# high_fre_amp.net
KiCad netlist of a schematic drawn in Altium Designer
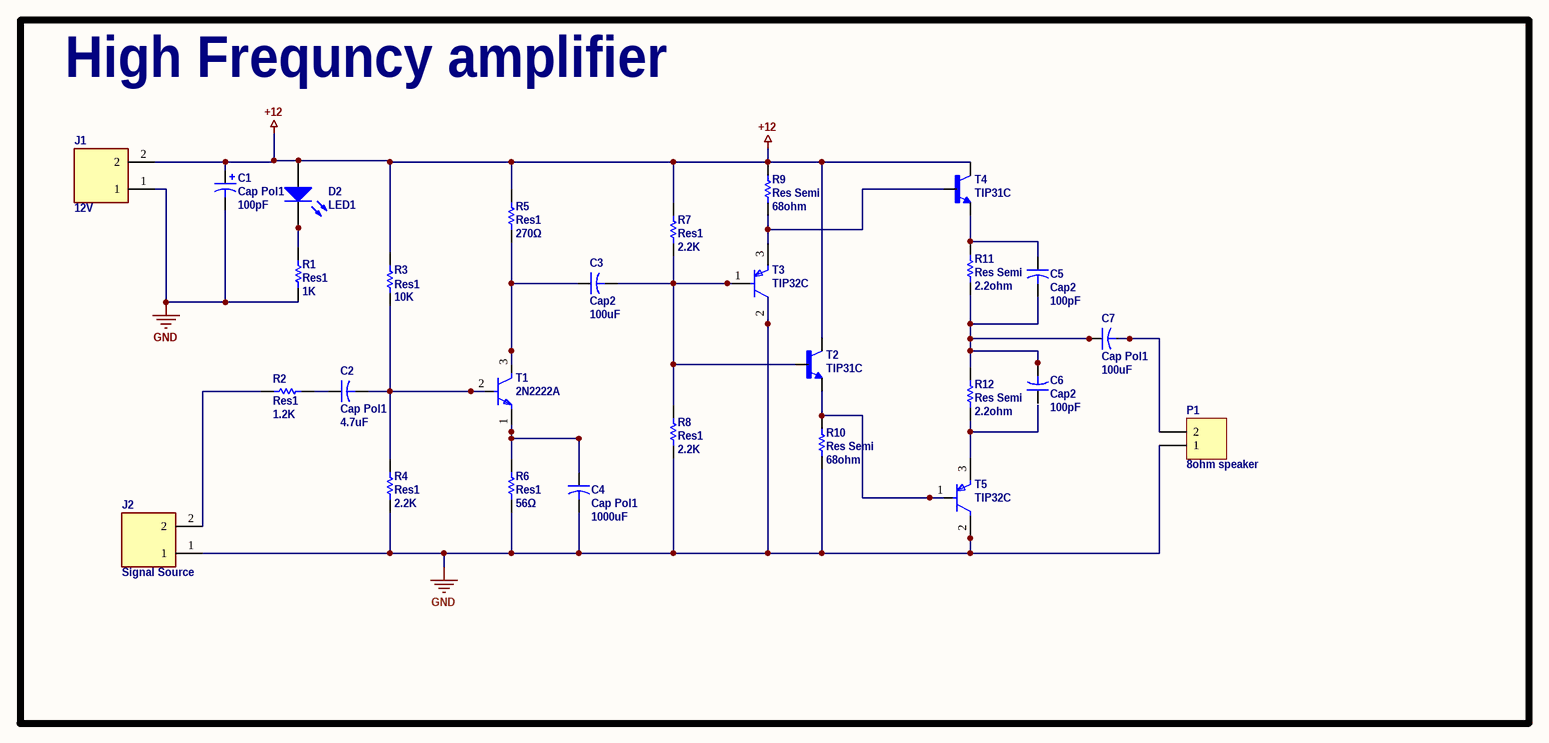
[diagram p0: high_fre_amp.SchDoc]

(export (version "E")
  (design (tool "Eeschema 10.0.6"))
  (components
    (comp (ref "C1")
      (value "Cap Pol1")
      (footprint "RB7.6-15")
      (description "Polarized Capacitor (Radial)")
      (fields (field (name "ALTIUM_VALUE") "100pF") (field (name "PUBLISHER") "Altium Limited"))
      (libsource (lib "Miscellaneous Devices") (part "Cap Pol1"))
    )
    (comp (ref "C2")
      (value "Cap Pol1")
      (footprint "RB7.6-15")
      (description "Capacitor")
      (fields (field (name "ALTIUM_VALUE") "4.7uF") (field (name "PUBLISHER") "Altium Limited"))
      (libsource (lib "Miscellaneous Devices") (part "Cap2"))
    )
    (comp (ref "C3")
      (value "Cap2")
      (footprint "CAPR5-4X5")
      (description "Capacitor")
      (fields (field (name "ALTIUM_VALUE") "100uF") (field (name "PUBLISHER") "Altium Limited"))
      (libsource (lib "Miscellaneous Devices") (part "Cap2"))
    )
    (comp (ref "C4")
      (value "Cap Pol1")
      (footprint "RB7.6-15")
      (description "Capacitor")
      (fields (field (name "ALTIUM_VALUE") "1000uF") (field (name "PUBLISHER") "Altium Limited"))
      (libsource (lib "Miscellaneous Devices") (part "Cap2"))
    )
    (comp (ref "C5")
      (value "Cap2")
      (footprint "CAPR5-4X5")
      (description "Capacitor")
      (fields (field (name "ALTIUM_VALUE") "100pF") (field (name "PUBLISHER") "Altium Limited"))
      (libsource (lib "Miscellaneous Devices") (part "Cap2"))
    )
    (comp (ref "C6")
      (value "Cap2")
      (footprint "CAPR5-4X5")
      (description "Capacitor")
      (fields (field (name "ALTIUM_VALUE") "100pF") (field (name "PUBLISHER") "Altium Limited"))
      (libsource (lib "Miscellaneous Devices") (part "Cap2"))
    )
    (comp (ref "C7")
      (value "Cap Pol1")
      (footprint "RB7.6-15")
      (description "Capacitor")
      (fields (field (name "ALTIUM_VALUE") "100uF") (field (name "PUBLISHER") "Altium Limited"))
      (libsource (lib "Miscellaneous Devices") (part "Cap2"))
    )
    (comp (ref "D2")
      (value "LED1")
      (footprint "LED-1")
      (description "Typical RED GaAs LED")
      (fields (field (name "PUBLISHER") "Altium Limited"))
      (libsource (lib "Miscellaneous Devices") (part "LED1"))
    )
    (comp (ref "J1")
      (value "12V")
      (footprint "HANDSON_KF301-2P")
      (description "2 Pin Terminal Block 5mm Pitch")
      (fields (field (name "MP") "KF301-2P"))
      (libsource (lib "KF301-2P") (part "KF301-2P"))
    )
    (comp (ref "J2")
      (value "Signal Source")
      (footprint "HANDSON_KF301-2P")
      (description "2 Pin Terminal Block 5mm Pitch")
      (fields (field (name "MP") "KF301-2P"))
      (libsource (lib "KF301-2P") (part "KF301-2P"))
    )
    (comp (ref "P1")
      (value "8ohm speaker")
      (footprint "HDR1X2")
      (description "Header, 2-Pin")
      (fields (field (name "PUBLISHER") "Altium Limited"))
      (libsource (lib "Miscellaneous Connectors") (part "Header 2"))
    )
    (comp (ref "R1")
      (value "Res1")
      (footprint "AXIAL-0.3")
      (description "Resistor")
      (fields (field (name "ALTIUM_VALUE") "1K") (field (name "PUBLISHER") "Altium Limited"))
      (libsource (lib "Miscellaneous Devices") (part "Res1"))
    )
    (comp (ref "R2")
      (value "Res1")
      (footprint "AXIAL-0.3")
      (description "Resistor")
      (fields (field (name "ALTIUM_VALUE") "1.2K") (field (name "PUBLISHER") "Altium Limited"))
      (libsource (lib "Miscellaneous Devices") (part "Res1"))
    )
    (comp (ref "R3")
      (value "Res1")
      (footprint "AXIAL-0.3")
      (description "Resistor")
      (fields (field (name "ALTIUM_VALUE") "10K") (field (name "PUBLISHER") "Altium Limited"))
      (libsource (lib "Miscellaneous Devices") (part "Res1"))
    )
    (comp (ref "R4")
      (value "Res1")
      (footprint "AXIAL-0.3")
      (description "Resistor")
      (fields (field (name "ALTIUM_VALUE") "2.2K") (field (name "PUBLISHER") "Altium Limited"))
      (libsource (lib "Miscellaneous Devices") (part "Res1"))
    )
    (comp (ref "R5")
      (value "Res1")
      (footprint "AXIAL-0.3")
      (description "Resistor")
      (fields (field (name "ALTIUM_VALUE") "270Ω") (field (name "PUBLISHER") "Altium Limited"))
      (libsource (lib "Miscellaneous Devices") (part "Res1"))
    )
    (comp (ref "R6")
      (value "Res1")
      (footprint "AXIAL-0.3")
      (description "Resistor")
      (fields (field (name "ALTIUM_VALUE") "56Ω") (field (name "PUBLISHER") "Altium Limited"))
      (libsource (lib "Miscellaneous Devices") (part "Res1"))
    )
    (comp (ref "R7")
      (value "Res1")
      (footprint "AXIAL-0.3")
      (description "Resistor")
      (fields (field (name "ALTIUM_VALUE") "2.2K") (field (name "PUBLISHER") "Altium Limited"))
      (libsource (lib "Miscellaneous Devices") (part "Res1"))
    )
    (comp (ref "R8")
      (value "Res1")
      (footprint "AXIAL-0.3")
      (description "Resistor")
      (fields (field (name "ALTIUM_VALUE") "2.2K") (field (name "PUBLISHER") "Altium Limited"))
      (libsource (lib "Miscellaneous Devices") (part "Res1"))
    )
    (comp (ref "R9")
      (value "Res Semi")
      (footprint "AXIAL-0.5")
      (description "Semiconductor Resistor")
      (fields (field (name "ALTIUM_VALUE") "68ohm") (field (name "PUBLISHER") "Altium Limited"))
      (libsource (lib "Miscellaneous Devices") (part "Res Semi"))
    )
    (comp (ref "R10")
      (value "Res Semi")
      (footprint "AXIAL-0.5")
      (description "Semiconductor Resistor")
      (fields (field (name "ALTIUM_VALUE") "68ohm") (field (name "PUBLISHER") "Altium Limited"))
      (libsource (lib "Miscellaneous Devices") (part "Res Semi"))
    )
    (comp (ref "R11")
      (value "Res Semi")
      (footprint "AXIAL-0.5")
      (description "Semiconductor Resistor")
      (fields (field (name "ALTIUM_VALUE") "2.2ohm") (field (name "PUBLISHER") "Altium Limited"))
      (libsource (lib "Miscellaneous Devices") (part "Res Semi"))
    )
    (comp (ref "R12")
      (value "Res Semi")
      (footprint "AXIAL-0.5")
      (description "Semiconductor Resistor")
      (fields (field (name "ALTIUM_VALUE") "2.2ohm") (field (name "PUBLISHER") "Altium Limited"))
      (libsource (lib "Miscellaneous Devices") (part "Res Semi"))
    )
    (comp (ref "T1")
      (value "2N2222A")
      (footprint "FP-2N2222A-MFG")
      (description "T-NPN SI- AUDIO VHF AMP")
      (libsource (lib "Altium Content Vault") (part "a64cbfbad643015290886283bc510aa"))
    )
    (comp (ref "T2")
      (value "TIP31C")
      (footprint "TO220")
      (description "Transistor bipolar (BJT) NPN 100 V 3 A 3 MHz 2 W Orificio pasante TO-220-3")
      (fields (field (name "MF") "ON Semiconductor") (field (name "DIGI-KEY_PART_NUMBER") "TIP31COS-ND"))
      (libsource (lib "TIP31C") (part "TIP31C"))
    )
    (comp (ref "T3")
      (value "TIP32C")
      (footprint "FP-TO-220-P0A0015988-MFG")
      (description "TRANS PNP 100V 3A TO-220")
      (fields
        (field (name "MANUFACTURER") "STMicroelectronics")
        (field (name "OCTOPART") "https://octopart.com/tip32c-stmicroelectronics-353617")
      )
      (libsource (lib "Altium Content Vault") (part "802a31d42ca070764d097f06bc9597f"))
    )
    (comp (ref "T4")
      (value "TIP31C")
      (footprint "TO220")
      (description "Transistor bipolar (BJT) NPN 100 V 3 A 3 MHz 2 W Orificio pasante TO-220-3")
      (fields (field (name "MF") "ON Semiconductor") (field (name "DIGI-KEY_PART_NUMBER") "TIP31COS-ND"))
      (libsource (lib "TIP31C") (part "TIP31C"))
    )
    (comp (ref "T5")
      (value "TIP32C")
      (footprint "FP-TO-220-P0A0015988-MFG")
      (description "TRANS PNP 100V 3A TO-220")
      (fields
        (field (name "MANUFACTURER") "STMicroelectronics")
        (field (name "OCTOPART") "https://octopart.com/tip32c-stmicroelectronics-353617")
      )
      (libsource (lib "Altium Content Vault") (part "802a31d42ca070764d097f06bc9597f"))
    )
  )
  (nets
    (net (code "1") (name "+12") (class "Default")
      (node (ref "C1") (pin "1") (pinfunction "1_1") (pintype "passive"))
      (node (ref "D2") (pin "1") (pinfunction "A_1") (pintype "passive"))
      (node (ref "J1") (pin "2") (pinfunction "2_2") (pintype "passive"))
      (node (ref "R3") (pin "2") (pinfunction "2_2") (pintype "passive"))
      (node (ref "R5") (pin "2") (pinfunction "2_2") (pintype "passive"))
      (node (ref "R7") (pin "2") (pinfunction "2_2") (pintype "passive"))
      (node (ref "R9") (pin "2") (pinfunction "2_2") (pintype "passive"))
      (node (ref "T2") (pin "2") (pinfunction "C_2") (pintype "passive"))
      (node (ref "T4") (pin "2") (pinfunction "C_2") (pintype "passive"))
    )
    (net (code "2") (name "GND") (class "Default")
      (node (ref "C1") (pin "2") (pinfunction "2_2") (pintype "passive"))
      (node (ref "C4") (pin "2") (pinfunction "2_2") (pintype "passive"))
      (node (ref "J1") (pin "1") (pinfunction "1_1") (pintype "passive"))
      (node (ref "J2") (pin "1") (pinfunction "1_1") (pintype "passive"))
      (node (ref "P1") (pin "1") (pinfunction "1_1") (pintype "passive"))
      (node (ref "R1") (pin "2") (pinfunction "2_2") (pintype "passive"))
      (node (ref "R10") (pin "1") (pinfunction "1_1") (pintype "passive"))
      (node (ref "R4") (pin "1") (pinfunction "1_1") (pintype "passive"))
      (node (ref "R6") (pin "1") (pinfunction "1_1") (pintype "passive"))
      (node (ref "R8") (pin "1") (pinfunction "1_1") (pintype "passive"))
      (node (ref "T3") (pin "2") (pinfunction "C_2") (pintype "passive"))
      (node (ref "T5") (pin "2") (pinfunction "C_2") (pintype "passive"))
    )
    (net (code "3") (name "Net-(C2-Pad1)") (class "Default")
      (node (ref "C2") (pin "1") (pinfunction "1_1") (pintype "passive"))
      (node (ref "R2") (pin "2") (pinfunction "2_2") (pintype "passive"))
    )
    (net (code "4") (name "Net-(C5-Pad2)") (class "Default")
      (node (ref "C5") (pin "2") (pinfunction "2_2") (pintype "passive"))
      (node (ref "C6") (pin "2") (pinfunction "2_2") (pintype "passive"))
      (node (ref "C7") (pin "1") (pinfunction "1_1") (pintype "passive"))
      (node (ref "R11") (pin "1") (pinfunction "1_1") (pintype "passive"))
      (node (ref "R12") (pin "2") (pinfunction "2_2") (pintype "passive"))
    )
    (net (code "5") (name "Net-(C7-Pad2)") (class "Default")
      (node (ref "C7") (pin "2") (pinfunction "2_2") (pintype "passive"))
      (node (ref "P1") (pin "2") (pinfunction "2_2") (pintype "passive"))
    )
    (net (code "6") (name "Net-(D2-K)") (class "Default")
      (node (ref "D2") (pin "2") (pinfunction "K_2") (pintype "passive"))
      (node (ref "R1") (pin "1") (pinfunction "1_1") (pintype "passive"))
    )
    (net (code "7") (name "Net-(J2-Pad2)") (class "Default")
      (node (ref "J2") (pin "2") (pinfunction "2_2") (pintype "passive"))
      (node (ref "R2") (pin "1") (pinfunction "1_1") (pintype "passive"))
    )
    (net (code "8") (name "Net-(T1-B)") (class "Default")
      (node (ref "C2") (pin "2") (pinfunction "2_2") (pintype "passive"))
      (node (ref "R3") (pin "1") (pinfunction "1_1") (pintype "passive"))
      (node (ref "R4") (pin "2") (pinfunction "2_2") (pintype "passive"))
      (node (ref "T1") (pin "2") (pinfunction "B_2") (pintype "passive"))
    )
    (net (code "9") (name "Net-(T1-C)") (class "Default")
      (node (ref "C3") (pin "1") (pinfunction "1_1") (pintype "passive"))
      (node (ref "R5") (pin "1") (pinfunction "1_1") (pintype "passive"))
      (node (ref "T1") (pin "3") (pinfunction "C_3") (pintype "passive"))
    )
    (net (code "10") (name "Net-(T1-E)") (class "Default")
      (node (ref "C4") (pin "1") (pinfunction "1_1") (pintype "passive"))
      (node (ref "R6") (pin "2") (pinfunction "2_2") (pintype "passive"))
      (node (ref "T1") (pin "1") (pinfunction "E_1") (pintype "passive"))
    )
    (net (code "11") (name "Net-(T2-B)") (class "Default")
      (node (ref "C3") (pin "2") (pinfunction "2_2") (pintype "passive"))
      (node (ref "R7") (pin "1") (pinfunction "1_1") (pintype "passive"))
      (node (ref "R8") (pin "2") (pinfunction "2_2") (pintype "passive"))
      (node (ref "T2") (pin "1") (pinfunction "B_1") (pintype "passive"))
      (node (ref "T3") (pin "1") (pinfunction "B_1") (pintype "passive"))
    )
    (net (code "12") (name "Net-(T2-E)") (class "Default")
      (node (ref "R10") (pin "2") (pinfunction "2_2") (pintype "passive"))
      (node (ref "T2") (pin "3") (pinfunction "E_3") (pintype "passive"))
      (node (ref "T5") (pin "1") (pinfunction "B_1") (pintype "passive"))
    )
    (net (code "13") (name "Net-(T3-E)") (class "Default")
      (node (ref "R9") (pin "1") (pinfunction "1_1") (pintype "passive"))
      (node (ref "T3") (pin "3") (pinfunction "E_3") (pintype "passive"))
      (node (ref "T4") (pin "1") (pinfunction "B_1") (pintype "passive"))
    )
    (net (code "14") (name "Net-(T4-E)") (class "Default")
      (node (ref "C5") (pin "1") (pinfunction "1_1") (pintype "passive"))
      (node (ref "R11") (pin "2") (pinfunction "2_2") (pintype "passive"))
      (node (ref "T4") (pin "3") (pinfunction "E_3") (pintype "passive"))
    )
    (net (code "15") (name "Net-(T5-E)") (class "Default")
      (node (ref "R12") (pin "1") (pinfunction "1_1") (pintype "passive"))
      (node (ref "T5") (pin "3") (pinfunction "E_3") (pintype "passive"))
    )
    (net (code "16") (name "unconnected-(C6-Pad1)") (class "Default")
      (node (ref "C6") (pin "1") (pinfunction "1_1") (pintype "passive"))
    )
  )
)
